# STM32.net
KiCad netlist of a schematic drawn in Altium Designer
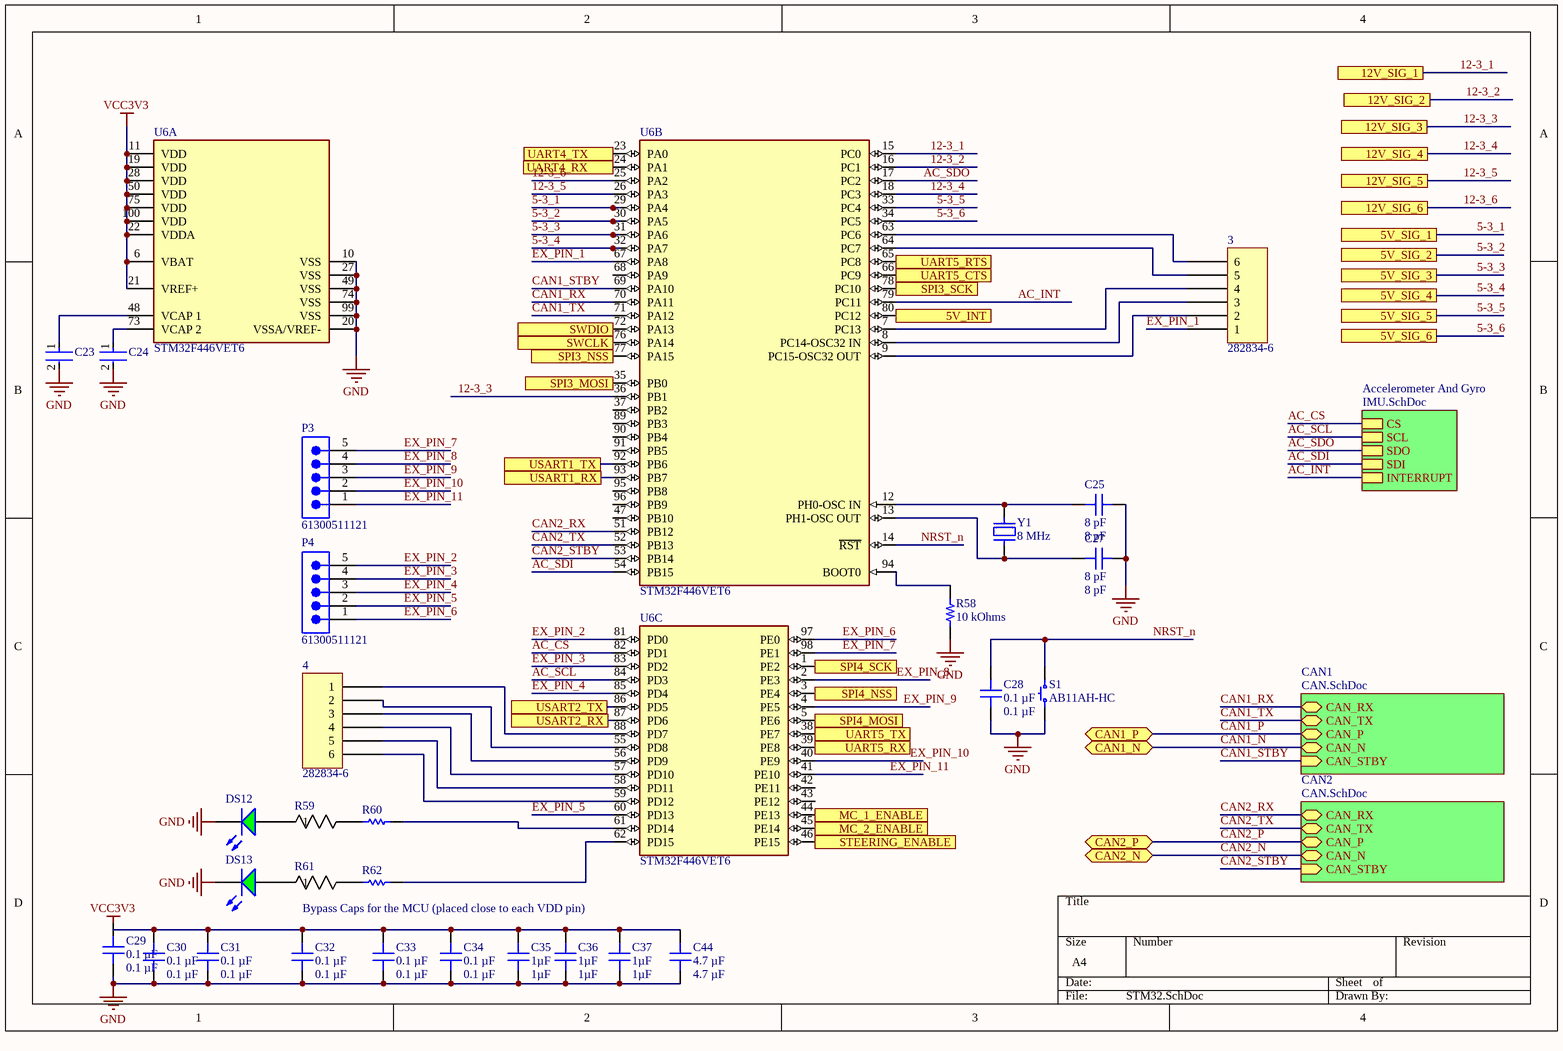
[diagram p0: STM32.SchDoc]

(export (version "E")
  (design (tool "Eeschema 10.0.6"))
  (components
    (comp (ref "3")
      (value "282834-6")
      (footprint "TE 282834-6")
      (description "TERM BLK 6P SIDE ENT 2.54MM PCB")
      (fields (field (name "MANUFACTURER") "TE Connectivity AMP Connectors") (field (name "VOLTAGE") "150V"))
      (libsource (lib "Celestial Altium Library - altium_library") (part "6 Pin"))
    )
    (comp (ref "4")
      (value "282834-6")
      (footprint "TE 282834-6")
      (description "TERM BLK 6P SIDE ENT 2.54MM PCB")
      (fields (field (name "MANUFACTURER") "TE Connectivity AMP Connectors") (field (name "VOLTAGE") "150V"))
      (libsource (lib "") (part "6 Pin_1"))
    )
    (comp (ref "C23")
      (value "GRM188R71A225KE15D")
      (footprint "FP-GRM188-0_1-e0_2_0_5-MFG")
      (description "Chip Multilayer Ceramic Capacitors for General Purpose, 0603, 2.2uF, X7R, 15%, 10%, 10V")
      (fields (field (name "VOLTAGE") "10V") (field (name "TOLERANCE") "10%"))
      (libsource (lib "Altium Content Vault") (part "11868f565c42a9108669ba33697ecf6"))
    )
    (comp (ref "C24")
      (value "GRM188R71A225KE15D")
      (footprint "FP-GRM188-0_1-e0_2_0_5-MFG")
      (description "Chip Multilayer Ceramic Capacitors for General Purpose, 0603, 2.2uF, X7R, 15%, 10%, 10V")
      (fields (field (name "VOLTAGE") "10V") (field (name "TOLERANCE") "10%"))
      (libsource (lib "Altium Content Vault") (part "11868f565c42a9108669ba33697ecf6"))
    )
    (comp (ref "C25")
      (value "8 pF")
      (footprint "CAP 0805_2012")
      (description "CAP CER 8PF 250V C0G/NP0 0805")
      (fields (field (name "PART NUMBER") "CBR08C809CAGAC") (field (name "ALTIUM_VALUE") "8 pF"))
      (libsource (lib "Celestial Altium Library - altium_library") (part "Capacitor"))
    )
    (comp (ref "C27")
      (value "8 pF")
      (footprint "CAP 0805_2012")
      (description "CAP CER 8PF 250V C0G/NP0 0805")
      (fields (field (name "PART NUMBER") "CBR08C809CAGAC") (field (name "ALTIUM_VALUE") "8 pF"))
      (libsource (lib "Celestial Altium Library - altium_library") (part "Capacitor"))
    )
    (comp (ref "C28")
      (value "0.1 µF")
      (footprint "CAP 0805_2012")
      (description "CAP CER 0.1UF 50V X7R 0805")
      (fields (field (name "PART NUMBER") "CC0805MRX7R9BB104") (field (name "ALTIUM_VALUE") "0.1 µF"))
      (libsource (lib "Celestial Altium Library - altium_library") (part "Capacitor"))
    )
    (comp (ref "C29")
      (value "0.1 µF")
      (footprint "CAP 0805_2012")
      (description "CAP CER 0.1UF 50V X7R 0805")
      (fields (field (name "PART NUMBER") "CC0805MRX7R9BB104") (field (name "ALTIUM_VALUE") "0.1 µF"))
      (libsource (lib "Celestial Altium Library - altium_library") (part "Capacitor"))
    )
    (comp (ref "C30")
      (value "0.1 µF")
      (footprint "CAP 0805_2012")
      (description "CAP CER 0.1UF 50V X7R 0805")
      (fields (field (name "PART NUMBER") "CC0805MRX7R9BB104") (field (name "ALTIUM_VALUE") "0.1 µF"))
      (libsource (lib "Celestial Altium Library - altium_library") (part "Capacitor"))
    )
    (comp (ref "C31")
      (value "0.1 µF")
      (footprint "CAP 0805_2012")
      (description "CAP CER 0.1UF 50V X7R 0805")
      (fields (field (name "PART NUMBER") "CC0805MRX7R9BB104") (field (name "ALTIUM_VALUE") "0.1 µF"))
      (libsource (lib "Celestial Altium Library - altium_library") (part "Capacitor"))
    )
    (comp (ref "C32")
      (value "0.1 µF")
      (footprint "CAP 0805_2012")
      (description "CAP CER 0.1UF 50V X7R 0805")
      (fields (field (name "PART NUMBER") "CC0805MRX7R9BB104") (field (name "ALTIUM_VALUE") "0.1 µF"))
      (libsource (lib "Celestial Altium Library - altium_library") (part "Capacitor"))
    )
    (comp (ref "C33")
      (value "0.1 µF")
      (footprint "CAP 0805_2012")
      (description "CAP CER 0.1UF 50V X7R 0805")
      (fields (field (name "PART NUMBER") "CC0805MRX7R9BB104") (field (name "ALTIUM_VALUE") "0.1 µF"))
      (libsource (lib "Celestial Altium Library - altium_library") (part "Capacitor"))
    )
    (comp (ref "C34")
      (value "0.1 µF")
      (footprint "CAP 0805_2012")
      (description "CAP CER 0.1UF 50V X7R 0805")
      (fields (field (name "PART NUMBER") "CC0805MRX7R9BB104") (field (name "ALTIUM_VALUE") "0.1 µF"))
      (libsource (lib "Celestial Altium Library - altium_library") (part "Capacitor"))
    )
    (comp (ref "C35")
      (value "1µF")
      (footprint "CAP 0805_2012")
      (description "CAP CER 1UF 10V X7R 0805")
      (fields (field (name "PART NUMBER") "MM05ZC105KCZ2A") (field (name "ALTIUM_VALUE") "1µF"))
      (libsource (lib "Celestial Altium Library - altium_library") (part "Capacitor"))
    )
    (comp (ref "C36")
      (value "1µF")
      (footprint "CAP 0805_2012")
      (description "CAP CER 1UF 10V X7R 0805")
      (fields (field (name "PART NUMBER") "MM05ZC105KCZ2A") (field (name "ALTIUM_VALUE") "1µF"))
      (libsource (lib "Celestial Altium Library - altium_library") (part "Capacitor"))
    )
    (comp (ref "C37")
      (value "1µF")
      (footprint "CAP 0805_2012")
      (description "CAP CER 1UF 10V X7R 0805")
      (fields (field (name "PART NUMBER") "MM05ZC105KCZ2A") (field (name "ALTIUM_VALUE") "1µF"))
      (libsource (lib "Celestial Altium Library - altium_library") (part "Capacitor"))
    )
    (comp (ref "C44")
      (value "4.7 µF")
      (footprint "CAP 0805_2012")
      (description "CAP CER 4.7UF 6.3V X7R 0805")
      (fields (field (name "PART NUMBER") "C0805X475J9RACAUTO") (field (name "ALTIUM_VALUE") "4.7 µF"))
      (libsource (lib "Celestial Altium Library - altium_library") (part "Capacitor"))
    )
    (comp (ref "DS12")
      (value "HLMP-4740")
      (footprint "AVAG-HLMP-4740")
      (description "T-1 3/4 (5 mm) Low Current LED Lamp, Green, 1.9 V, -20 to 100 degC, 2-Pin THD, RoHS, Bulk")
      (fields (field (name "MANUFACTURER") "AvagoTechnologies"))
      (libsource (lib "Altium Content Vault") (part "LED-GREEN-AK-2"))
    )
    (comp (ref "DS13")
      (value "HLMP-4740")
      (footprint "AVAG-HLMP-4740")
      (description "T-1 3/4 (5 mm) Low Current LED Lamp, Green, 1.9 V, -20 to 100 degC, 2-Pin THD, RoHS, Bulk")
      (fields (field (name "MANUFACTURER") "AvagoTechnologies"))
      (libsource (lib "Altium Content Vault") (part "LED-GREEN-AK-2"))
    )
    (comp (ref "P3")
      (value "61300511121")
      (footprint "61300511121")
      (libsource (lib "Altium Content Vault") (part "Header_Male_1R_05P"))
    )
    (comp (ref "P4")
      (value "61300511121")
      (footprint "61300511121")
      (libsource (lib "Altium Content Vault") (part "Header_Male_1R_05P"))
    )
    (comp (ref "R58")
      (value "10 kOhms")
      (footprint "RES 0805_2012")
      (description "RES 10K OHM 0.1% 1/10W 0805")
      (fields
        (field (name "PART NUMBER") "RNCS0805BKE10K0")
        (field (name "MANUFACTURER") "Stackpole Electronics Inc")
      )
      (libsource (lib "Celestial Altium Library - altium_library") (part "Resistor"))
    )
    (comp (ref "R59")
      (value "AC01000005000JA100")
      (footprint "RES_AC01_VIS")
      (fields (field (name "TOLERANCE") "5%"))
      (libsource (lib "Altium Content Vault") (part "AC01000005000JA100"))
    )
    (comp (ref "R60")
      (value "RC0805FR-071KL")
      (footprint "RESC2013X60X35ML10T20")
      (description "Chip Resistor, 1 KOhm, +/- 1%, 125 mW, -55 to 155 degC, 0805 (2012 Metric), RoHS, Tape and Reel")
      (fields (field (name "TOLERANCE") "1%") (field (name "MANUFACTURER") "Yageo"))
      (libsource (lib "Altium Content Vault") (part "RES-2"))
    )
    (comp (ref "R61")
      (value "AC01000005000JA100")
      (footprint "RES_AC01_VIS")
      (fields (field (name "TOLERANCE") "5%"))
      (libsource (lib "Altium Content Vault") (part "AC01000005000JA100"))
    )
    (comp (ref "R62")
      (value "RC0805FR-071KL")
      (footprint "RESC2013X60X35ML10T20")
      (description "Chip Resistor, 1 KOhm, +/- 1%, 125 mW, -55 to 155 degC, 0805 (2012 Metric), RoHS, Tape and Reel")
      (fields (field (name "TOLERANCE") "1%") (field (name "MANUFACTURER") "Yageo"))
      (libsource (lib "Altium Content Vault") (part "RES-2"))
    )
    (comp (ref "S1")
      (value "AB11AH-HC")
      (footprint "NKK AB11AH-HC")
      (description "SWITCH PUSH SPST-NO 0.4VA 28V")
      (fields (field (name "MANUFACTURER") "NKK Switches"))
      (libsource (lib "Celestial Altium Library - altium_library") (part "SPST-NO 2 PIN"))
    )
    (comp (ref "U6")
      (value "STM32F446VET6")
      (footprint "FP-LQFP100-1L-MFG")
      (description "IC MCU 32BIT 512KB FLASH 100LQFP")
      (fields
        (field (name "OCTOPART") "https://octopart.com/stm32f446vet6-stmicroelectronics-52642922")
        (field (name "MANUFACTURER") "STMicroelectronics")
      )
      (libsource (lib "Altium Content Vault") (part "8e3e88e6cb74ec1f9e49940598abbc7"))
    )
    (comp (ref "Y1")
      (value "8 MHz")
      (footprint "ABRACON ABLS")
      (description "CRYSTAL 8.0000MHZ 18PF SMD")
      (fields (field (name "PART NUMBER") "ABLS-8.000MHZ-SD7Y-T") (field (name "MANUFACTURER") "Abracon LLC"))
      (libsource (lib "Celestial Altium Library - altium_library") (part "Abracon Crystal ABLS"))
    )
  )
  (nets
    (net (code "1") (name "/5-3_1") (class "Default")
      (node (ref "U6") (pin "29") (pinfunction "PA4_29") (pintype "bidirectional"))
    )
    (net (code "2") (name "/5-3_2") (class "Default")
      (node (ref "U6") (pin "30") (pinfunction "PA5_30") (pintype "bidirectional"))
    )
    (net (code "3") (name "/5-3_3") (class "Default")
      (node (ref "U6") (pin "31") (pinfunction "PA6_31") (pintype "bidirectional"))
    )
    (net (code "4") (name "/5-3_4") (class "Default")
      (node (ref "U6") (pin "32") (pinfunction "PA7_32") (pintype "bidirectional"))
    )
    (net (code "5") (name "/5-3_5") (class "Default")
      (node (ref "U6") (pin "33") (pinfunction "PC4_33") (pintype "bidirectional"))
    )
    (net (code "6") (name "/5-3_6") (class "Default")
      (node (ref "U6") (pin "34") (pinfunction "PC5_34") (pintype "bidirectional"))
    )
    (net (code "7") (name "/5V_INT") (class "Default")
      (node (ref "U6") (pin "80") (pinfunction "PC12_80") (pintype "bidirectional"))
    )
    (net (code "8") (name "/12-3_1") (class "Default")
      (node (ref "U6") (pin "15") (pinfunction "PC0_15") (pintype "bidirectional"))
    )
    (net (code "9") (name "/12-3_2") (class "Default")
      (node (ref "U6") (pin "16") (pinfunction "PC1_16") (pintype "bidirectional"))
    )
    (net (code "10") (name "/12-3_3") (class "Default")
      (node (ref "U6") (pin "36") (pinfunction "PB1_36") (pintype "bidirectional"))
    )
    (net (code "11") (name "/12-3_4") (class "Default")
      (node (ref "U6") (pin "18") (pinfunction "PC3_18") (pintype "bidirectional"))
    )
    (net (code "12") (name "/12-3_5") (class "Default")
      (node (ref "U6") (pin "26") (pinfunction "PA3_26") (pintype "bidirectional"))
    )
    (net (code "13") (name "/12-3_6") (class "Default")
      (node (ref "U6") (pin "25") (pinfunction "PA2_25") (pintype "bidirectional"))
    )
    (net (code "14") (name "/AC_CS") (class "Default")
      (node (ref "U6") (pin "82") (pinfunction "PD1_82") (pintype "bidirectional"))
    )
    (net (code "15") (name "/AC_INT") (class "Default")
      (node (ref "U6") (pin "79") (pinfunction "PC11_79") (pintype "bidirectional"))
    )
    (net (code "16") (name "/AC_SCL") (class "Default")
      (node (ref "U6") (pin "84") (pinfunction "PD3_84") (pintype "bidirectional"))
    )
    (net (code "17") (name "/AC_SDI") (class "Default")
      (node (ref "U6") (pin "54") (pinfunction "PB15_54") (pintype "bidirectional"))
    )
    (net (code "18") (name "/AC_SDO") (class "Default")
      (node (ref "U6") (pin "17") (pinfunction "PC2_17") (pintype "bidirectional"))
    )
    (net (code "21") (name "/CAN1_RX") (class "Default")
      (node (ref "U6") (pin "70") (pinfunction "PA11_70") (pintype "bidirectional"))
    )
    (net (code "22") (name "/CAN1_STBY") (class "Default")
      (node (ref "U6") (pin "69") (pinfunction "PA10_69") (pintype "bidirectional"))
    )
    (net (code "23") (name "/CAN1_TX") (class "Default")
      (node (ref "U6") (pin "71") (pinfunction "PA12_71") (pintype "bidirectional"))
    )
    (net (code "26") (name "/CAN2_RX") (class "Default")
      (node (ref "U6") (pin "51") (pinfunction "PB12_51") (pintype "bidirectional"))
    )
    (net (code "27") (name "/CAN2_STBY") (class "Default")
      (node (ref "U6") (pin "53") (pinfunction "PB14_53") (pintype "bidirectional"))
    )
    (net (code "28") (name "/CAN2_TX") (class "Default")
      (node (ref "U6") (pin "52") (pinfunction "PB13_52") (pintype "bidirectional"))
    )
    (net (code "29") (name "/EX_PIN_1") (class "Default")
      (node (ref "3") (pin "1") (pinfunction "1_1") (pintype "passive"))
      (node (ref "U6") (pin "67") (pinfunction "PA8_67") (pintype "bidirectional"))
    )
    (net (code "30") (name "/EX_PIN_2") (class "Default")
      (node (ref "P4") (pin "5") (pinfunction "5_5") (pintype "passive"))
      (node (ref "U6") (pin "81") (pinfunction "PD0_81") (pintype "bidirectional"))
    )
    (net (code "31") (name "/EX_PIN_3") (class "Default")
      (node (ref "P4") (pin "4") (pinfunction "4_4") (pintype "passive"))
      (node (ref "U6") (pin "83") (pinfunction "PD2_83") (pintype "bidirectional"))
    )
    (net (code "32") (name "/EX_PIN_4") (class "Default")
      (node (ref "P4") (pin "3") (pinfunction "3_3") (pintype "passive"))
      (node (ref "U6") (pin "85") (pinfunction "PD4_85") (pintype "bidirectional"))
    )
    (net (code "33") (name "/EX_PIN_5") (class "Default")
      (node (ref "P4") (pin "2") (pinfunction "2_2") (pintype "passive"))
      (node (ref "U6") (pin "60") (pinfunction "PD13_60") (pintype "bidirectional"))
    )
    (net (code "34") (name "/EX_PIN_6") (class "Default")
      (node (ref "P4") (pin "1") (pinfunction "1_1") (pintype "passive"))
      (node (ref "U6") (pin "97") (pinfunction "PE0_97") (pintype "bidirectional"))
    )
    (net (code "35") (name "/EX_PIN_7") (class "Default")
      (node (ref "P3") (pin "5") (pinfunction "5_5") (pintype "passive"))
      (node (ref "U6") (pin "98") (pinfunction "PE1_98") (pintype "bidirectional"))
    )
    (net (code "36") (name "/EX_PIN_8") (class "Default")
      (node (ref "P3") (pin "4") (pinfunction "4_4") (pintype "passive"))
      (node (ref "U6") (pin "2") (pinfunction "PE3_2") (pintype "bidirectional"))
    )
    (net (code "37") (name "/EX_PIN_9") (class "Default")
      (node (ref "P3") (pin "3") (pinfunction "3_3") (pintype "passive"))
      (node (ref "U6") (pin "4") (pinfunction "PE5_4") (pintype "bidirectional"))
    )
    (net (code "38") (name "/EX_PIN_10") (class "Default")
      (node (ref "P3") (pin "2") (pinfunction "2_2") (pintype "passive"))
      (node (ref "U6") (pin "40") (pinfunction "PE9_40") (pintype "bidirectional"))
    )
    (net (code "39") (name "/EX_PIN_11") (class "Default")
      (node (ref "P3") (pin "1") (pinfunction "1_1") (pintype "passive"))
      (node (ref "U6") (pin "41") (pinfunction "PE10_41") (pintype "bidirectional"))
    )
    (net (code "40") (name "/MC_1_ENABLE") (class "Default")
      (node (ref "U6") (pin "44") (pinfunction "PE13_44") (pintype "bidirectional"))
    )
    (net (code "41") (name "/MC_2_ENABLE") (class "Default")
      (node (ref "U6") (pin "45") (pinfunction "PE14_45") (pintype "bidirectional"))
    )
    (net (code "42") (name "/NRST_n") (class "Default")
      (node (ref "C28") (pin "2") (pinfunction "2_2") (pintype "passive"))
      (node (ref "S1") (pin "2") (pinfunction "2_2") (pintype "passive"))
      (node (ref "U6") (pin "14") (pinfunction "~{RST}_14") (pintype "bidirectional"))
    )
    (net (code "43") (name "/SPI3_MOSI") (class "Default")
      (node (ref "U6") (pin "35") (pinfunction "PB0_35") (pintype "bidirectional"))
    )
    (net (code "44") (name "/SPI3_NSS") (class "Default")
      (node (ref "U6") (pin "77") (pinfunction "PA15_77") (pintype "bidirectional"))
    )
    (net (code "45") (name "/SPI3_SCK") (class "Default")
      (node (ref "U6") (pin "78") (pinfunction "PC10_78") (pintype "bidirectional"))
    )
    (net (code "46") (name "/SPI4_MOSI") (class "Default")
      (node (ref "U6") (pin "5") (pinfunction "PE6_5") (pintype "bidirectional"))
    )
    (net (code "47") (name "/SPI4_NSS") (class "Default")
      (node (ref "U6") (pin "3") (pinfunction "PE4_3") (pintype "bidirectional"))
    )
    (net (code "48") (name "/SPI4_SCK") (class "Default")
      (node (ref "U6") (pin "1") (pinfunction "PE2_1") (pintype "bidirectional"))
    )
    (net (code "49") (name "/STEERING_ENABLE") (class "Default")
      (node (ref "U6") (pin "46") (pinfunction "PE15_46") (pintype "bidirectional"))
    )
    (net (code "50") (name "/SWCLK") (class "Default")
      (node (ref "U6") (pin "76") (pinfunction "PA14_76") (pintype "bidirectional"))
    )
    (net (code "51") (name "/SWDIO") (class "Default")
      (node (ref "U6") (pin "72") (pinfunction "PA13_72") (pintype "bidirectional"))
    )
    (net (code "52") (name "/UART4_RX") (class "Default")
      (node (ref "U6") (pin "24") (pinfunction "PA1_24") (pintype "bidirectional"))
    )
    (net (code "53") (name "/UART4_TX") (class "Default")
      (node (ref "U6") (pin "23") (pinfunction "PA0_23") (pintype "bidirectional"))
    )
    (net (code "54") (name "/UART5_CTS") (class "Default")
      (node (ref "U6") (pin "66") (pinfunction "PC9_66") (pintype "bidirectional"))
    )
    (net (code "55") (name "/UART5_RTS") (class "Default")
      (node (ref "U6") (pin "65") (pinfunction "PC8_65") (pintype "bidirectional"))
    )
    (net (code "56") (name "/UART5_RX") (class "Default")
      (node (ref "U6") (pin "39") (pinfunction "PE8_39") (pintype "bidirectional"))
    )
    (net (code "57") (name "/UART5_TX") (class "Default")
      (node (ref "U6") (pin "38") (pinfunction "PE7_38") (pintype "bidirectional"))
    )
    (net (code "58") (name "/USART1_RX") (class "Default")
      (node (ref "U6") (pin "93") (pinfunction "PB7_93") (pintype "bidirectional"))
    )
    (net (code "59") (name "/USART1_TX") (class "Default")
      (node (ref "U6") (pin "92") (pinfunction "PB6_92") (pintype "bidirectional"))
    )
    (net (code "60") (name "/USART2_RX") (class "Default")
      (node (ref "U6") (pin "87") (pinfunction "PD6_87") (pintype "bidirectional"))
    )
    (net (code "61") (name "/USART2_TX") (class "Default")
      (node (ref "U6") (pin "86") (pinfunction "PD5_86") (pintype "bidirectional"))
    )
    (net (code "62") (name "GND") (class "Default")
      (node (ref "C23") (pin "2") (pinfunction "2_2") (pintype "passive"))
      (node (ref "C24") (pin "2") (pinfunction "2_2") (pintype "passive"))
      (node (ref "C25") (pin "2") (pinfunction "2_2") (pintype "passive"))
      (node (ref "C27") (pin "2") (pinfunction "2_2") (pintype "passive"))
      (node (ref "C28") (pin "1") (pinfunction "1_1") (pintype "passive"))
      (node (ref "C29") (pin "1") (pinfunction "1_1") (pintype "passive"))
      (node (ref "C30") (pin "1") (pinfunction "1_1") (pintype "passive"))
      (node (ref "C31") (pin "1") (pinfunction "1_1") (pintype "passive"))
      (node (ref "C32") (pin "1") (pinfunction "1_1") (pintype "passive"))
      (node (ref "C33") (pin "1") (pinfunction "1_1") (pintype "passive"))
      (node (ref "C34") (pin "1") (pinfunction "1_1") (pintype "passive"))
      (node (ref "C35") (pin "1") (pinfunction "1_1") (pintype "passive"))
      (node (ref "C36") (pin "1") (pinfunction "1_1") (pintype "passive"))
      (node (ref "C37") (pin "1") (pinfunction "1_1") (pintype "passive"))
      (node (ref "C44") (pin "1") (pinfunction "1_1") (pintype "passive"))
      (node (ref "DS12") (pin "2") (pinfunction "K_2") (pintype "passive"))
      (node (ref "DS13") (pin "2") (pinfunction "K_2") (pintype "passive"))
      (node (ref "R58") (pin "1") (pinfunction "1_1") (pintype "passive"))
      (node (ref "S1") (pin "1") (pinfunction "1_1") (pintype "passive"))
      (node (ref "U6") (pin "10") (pinfunction "VSS_10") (pintype "power_in"))
      (node (ref "U6") (pin "20") (pinfunction "VSSA/VREF-_20") (pintype "power_in"))
      (node (ref "U6") (pin "27") (pinfunction "VSS_27") (pintype "power_in"))
      (node (ref "U6") (pin "49") (pinfunction "VSS_49") (pintype "power_in"))
      (node (ref "U6") (pin "74") (pinfunction "VSS_74") (pintype "power_in"))
      (node (ref "U6") (pin "99") (pinfunction "VSS_99") (pintype "power_in"))
    )
    (net (code "63") (name "Net-(DS12-A)") (class "Default")
      (node (ref "DS12") (pin "1") (pinfunction "A_1") (pintype "passive"))
      (node (ref "R59") (pin "1") (pinfunction "1_1") (pintype "passive"))
    )
    (net (code "64") (name "Net-(DS13-A)") (class "Default")
      (node (ref "DS13") (pin "1") (pinfunction "A_1") (pintype "passive"))
      (node (ref "R61") (pin "1") (pinfunction "1_1") (pintype "passive"))
    )
    (net (code "65") (name "Net-(R59-Pad2)") (class "Default")
      (node (ref "R59") (pin "2") (pinfunction "2_2") (pintype "passive"))
      (node (ref "R60") (pin "1") (pinfunction "1_1") (pintype "passive"))
    )
    (net (code "66") (name "Net-(R61-Pad2)") (class "Default")
      (node (ref "R61") (pin "2") (pinfunction "2_2") (pintype "passive"))
      (node (ref "R62") (pin "1") (pinfunction "1_1") (pintype "passive"))
    )
    (net (code "67") (name "Net-(U6A-VCAP_1)") (class "Default")
      (node (ref "C23") (pin "1") (pinfunction "1_1") (pintype "passive"))
      (node (ref "U6") (pin "48") (pinfunction "VCAP_1_48") (pintype "power_in"))
    )
    (net (code "68") (name "Net-(U6A-VCAP_2)") (class "Default")
      (node (ref "C24") (pin "1") (pinfunction "1_1") (pintype "passive"))
      (node (ref "U6") (pin "73") (pinfunction "VCAP_2_73") (pintype "power_in"))
    )
    (net (code "69") (name "Net-(U6B-BOOT0)") (class "Default")
      (node (ref "R58") (pin "2") (pinfunction "2_2") (pintype "passive"))
      (node (ref "U6") (pin "94") (pinfunction "BOOT0_94") (pintype "input"))
    )
    (net (code "70") (name "Net-(U6B-PC6)") (class "Default")
      (node (ref "3") (pin "6") (pinfunction "6_6") (pintype "passive"))
      (node (ref "U6") (pin "63") (pinfunction "PC6_63") (pintype "bidirectional"))
    )
    (net (code "71") (name "Net-(U6B-PC7)") (class "Default")
      (node (ref "3") (pin "5") (pinfunction "5_5") (pintype "passive"))
      (node (ref "U6") (pin "64") (pinfunction "PC7_64") (pintype "bidirectional"))
    )
    (net (code "72") (name "Net-(U6B-PC13)") (class "Default")
      (node (ref "3") (pin "4") (pinfunction "4_4") (pintype "passive"))
      (node (ref "U6") (pin "7") (pinfunction "PC13_7") (pintype "bidirectional"))
    )
    (net (code "73") (name "Net-(U6B-PC14-OSC32_IN)") (class "Default")
      (node (ref "3") (pin "3") (pinfunction "3_3") (pintype "passive"))
      (node (ref "U6") (pin "8") (pinfunction "PC14-OSC32_IN_8") (pintype "bidirectional"))
    )
    (net (code "74") (name "Net-(U6B-PC15-OSC32_OUT)") (class "Default")
      (node (ref "3") (pin "2") (pinfunction "2_2") (pintype "passive"))
      (node (ref "U6") (pin "9") (pinfunction "PC15-OSC32_OUT_9") (pintype "bidirectional"))
    )
    (net (code "75") (name "Net-(U6B-PH0-OSC_IN)") (class "Default")
      (node (ref "C25") (pin "1") (pinfunction "1_1") (pintype "passive"))
      (node (ref "U6") (pin "12") (pinfunction "PH0-OSC_IN_12") (pintype "input"))
      (node (ref "Y1") (pin "2") (pinfunction "2_2") (pintype "passive"))
    )
    (net (code "76") (name "Net-(U6B-PH1-OSC_OUT)") (class "Default")
      (node (ref "C27") (pin "1") (pinfunction "1_1") (pintype "passive"))
      (node (ref "U6") (pin "13") (pinfunction "PH1-OSC_OUT_13") (pintype "bidirectional"))
      (node (ref "Y1") (pin "1") (pinfunction "1_1") (pintype "passive"))
    )
    (net (code "77") (name "Net-(U6C-PD7)") (class "Default")
      (node (ref "4") (pin "1") (pinfunction "1_1") (pintype "passive"))
      (node (ref "U6") (pin "88") (pinfunction "PD7_88") (pintype "bidirectional"))
    )
    (net (code "78") (name "Net-(U6C-PD8)") (class "Default")
      (node (ref "4") (pin "2") (pinfunction "2_2") (pintype "passive"))
      (node (ref "U6") (pin "55") (pinfunction "PD8_55") (pintype "bidirectional"))
    )
    (net (code "79") (name "Net-(U6C-PD9)") (class "Default")
      (node (ref "4") (pin "3") (pinfunction "3_3") (pintype "passive"))
      (node (ref "U6") (pin "56") (pinfunction "PD9_56") (pintype "bidirectional"))
    )
    (net (code "80") (name "Net-(U6C-PD10)") (class "Default")
      (node (ref "4") (pin "4") (pinfunction "4_4") (pintype "passive"))
      (node (ref "U6") (pin "57") (pinfunction "PD10_57") (pintype "bidirectional"))
    )
    (net (code "81") (name "Net-(U6C-PD11)") (class "Default")
      (node (ref "4") (pin "5") (pinfunction "5_5") (pintype "passive"))
      (node (ref "U6") (pin "58") (pinfunction "PD11_58") (pintype "bidirectional"))
    )
    (net (code "82") (name "Net-(U6C-PD12)") (class "Default")
      (node (ref "4") (pin "6") (pinfunction "6_6") (pintype "passive"))
      (node (ref "U6") (pin "59") (pinfunction "PD12_59") (pintype "bidirectional"))
    )
    (net (code "83") (name "Net-(U6C-PD14)") (class "Default")
      (node (ref "R60") (pin "2") (pinfunction "2_2") (pintype "passive"))
      (node (ref "U6") (pin "61") (pinfunction "PD14_61") (pintype "bidirectional"))
    )
    (net (code "84") (name "Net-(U6C-PD15)") (class "Default")
      (node (ref "R62") (pin "2") (pinfunction "2_2") (pintype "passive"))
      (node (ref "U6") (pin "62") (pinfunction "PD15_62") (pintype "bidirectional"))
    )
    (net (code "85") (name "VCC3V3") (class "Default")
      (node (ref "C30") (pin "2") (pinfunction "2_2") (pintype "passive"))
      (node (ref "C31") (pin "2") (pinfunction "2_2") (pintype "passive"))
      (node (ref "C32") (pin "2") (pinfunction "2_2") (pintype "passive"))
      (node (ref "C33") (pin "2") (pinfunction "2_2") (pintype "passive"))
      (node (ref "C34") (pin "2") (pinfunction "2_2") (pintype "passive"))
      (node (ref "C35") (pin "2") (pinfunction "2_2") (pintype "passive"))
      (node (ref "C36") (pin "2") (pinfunction "2_2") (pintype "passive"))
      (node (ref "C37") (pin "2") (pinfunction "2_2") (pintype "passive"))
      (node (ref "C44") (pin "2") (pinfunction "2_2") (pintype "passive"))
      (node (ref "U6") (pin "100") (pinfunction "VDD_100") (pintype "power_in"))
      (node (ref "U6") (pin "11") (pinfunction "VDD_11") (pintype "power_in"))
      (node (ref "U6") (pin "19") (pinfunction "VDD_19") (pintype "power_in"))
      (node (ref "U6") (pin "21") (pinfunction "VREF+_21") (pintype "power_in"))
      (node (ref "U6") (pin "22") (pinfunction "VDDA_22") (pintype "power_in"))
      (node (ref "U6") (pin "28") (pinfunction "VDD_28") (pintype "power_in"))
      (node (ref "U6") (pin "50") (pinfunction "VDD_50") (pintype "power_in"))
      (node (ref "U6") (pin "6") (pinfunction "VBAT_6") (pintype "power_in"))
      (node (ref "U6") (pin "75") (pinfunction "VDD_75") (pintype "power_in"))
    )
    (net (code "86") (name "unconnected-(C29-Pad2)") (class "Default")
      (node (ref "C29") (pin "2") (pinfunction "2_2") (pintype "passive"))
    )
    (net (code "87") (name "unconnected-(U6B-PA9-Pad68)") (class "Default")
      (node (ref "U6") (pin "68") (pinfunction "PA9_68") (pintype "bidirectional"))
    )
    (net (code "88") (name "unconnected-(U6B-PB2-Pad37)") (class "Default")
      (node (ref "U6") (pin "37") (pinfunction "PB2_37") (pintype "bidirectional"))
    )
    (net (code "89") (name "unconnected-(U6B-PB3-Pad89)") (class "Default")
      (node (ref "U6") (pin "89") (pinfunction "PB3_89") (pintype "bidirectional"))
    )
    (net (code "90") (name "unconnected-(U6B-PB4-Pad90)") (class "Default")
      (node (ref "U6") (pin "90") (pinfunction "PB4_90") (pintype "bidirectional"))
    )
    (net (code "91") (name "unconnected-(U6B-PB5-Pad91)") (class "Default")
      (node (ref "U6") (pin "91") (pinfunction "PB5_91") (pintype "bidirectional"))
    )
    (net (code "92") (name "unconnected-(U6B-PB8-Pad95)") (class "Default")
      (node (ref "U6") (pin "95") (pinfunction "PB8_95") (pintype "bidirectional"))
    )
    (net (code "93") (name "unconnected-(U6B-PB9-Pad96)") (class "Default")
      (node (ref "U6") (pin "96") (pinfunction "PB9_96") (pintype "bidirectional"))
    )
    (net (code "94") (name "unconnected-(U6B-PB10-Pad47)") (class "Default")
      (node (ref "U6") (pin "47") (pinfunction "PB10_47") (pintype "bidirectional"))
    )
    (net (code "95") (name "unconnected-(U6C-PE11-Pad42)") (class "Default")
      (node (ref "U6") (pin "42") (pinfunction "PE11_42") (pintype "bidirectional"))
    )
    (net (code "96") (name "unconnected-(U6C-PE12-Pad43)") (class "Default")
      (node (ref "U6") (pin "43") (pinfunction "PE12_43") (pintype "bidirectional"))
    )
  )
)
